# power-converter.net
KiCad netlist of a schematic drawn in EAGLE
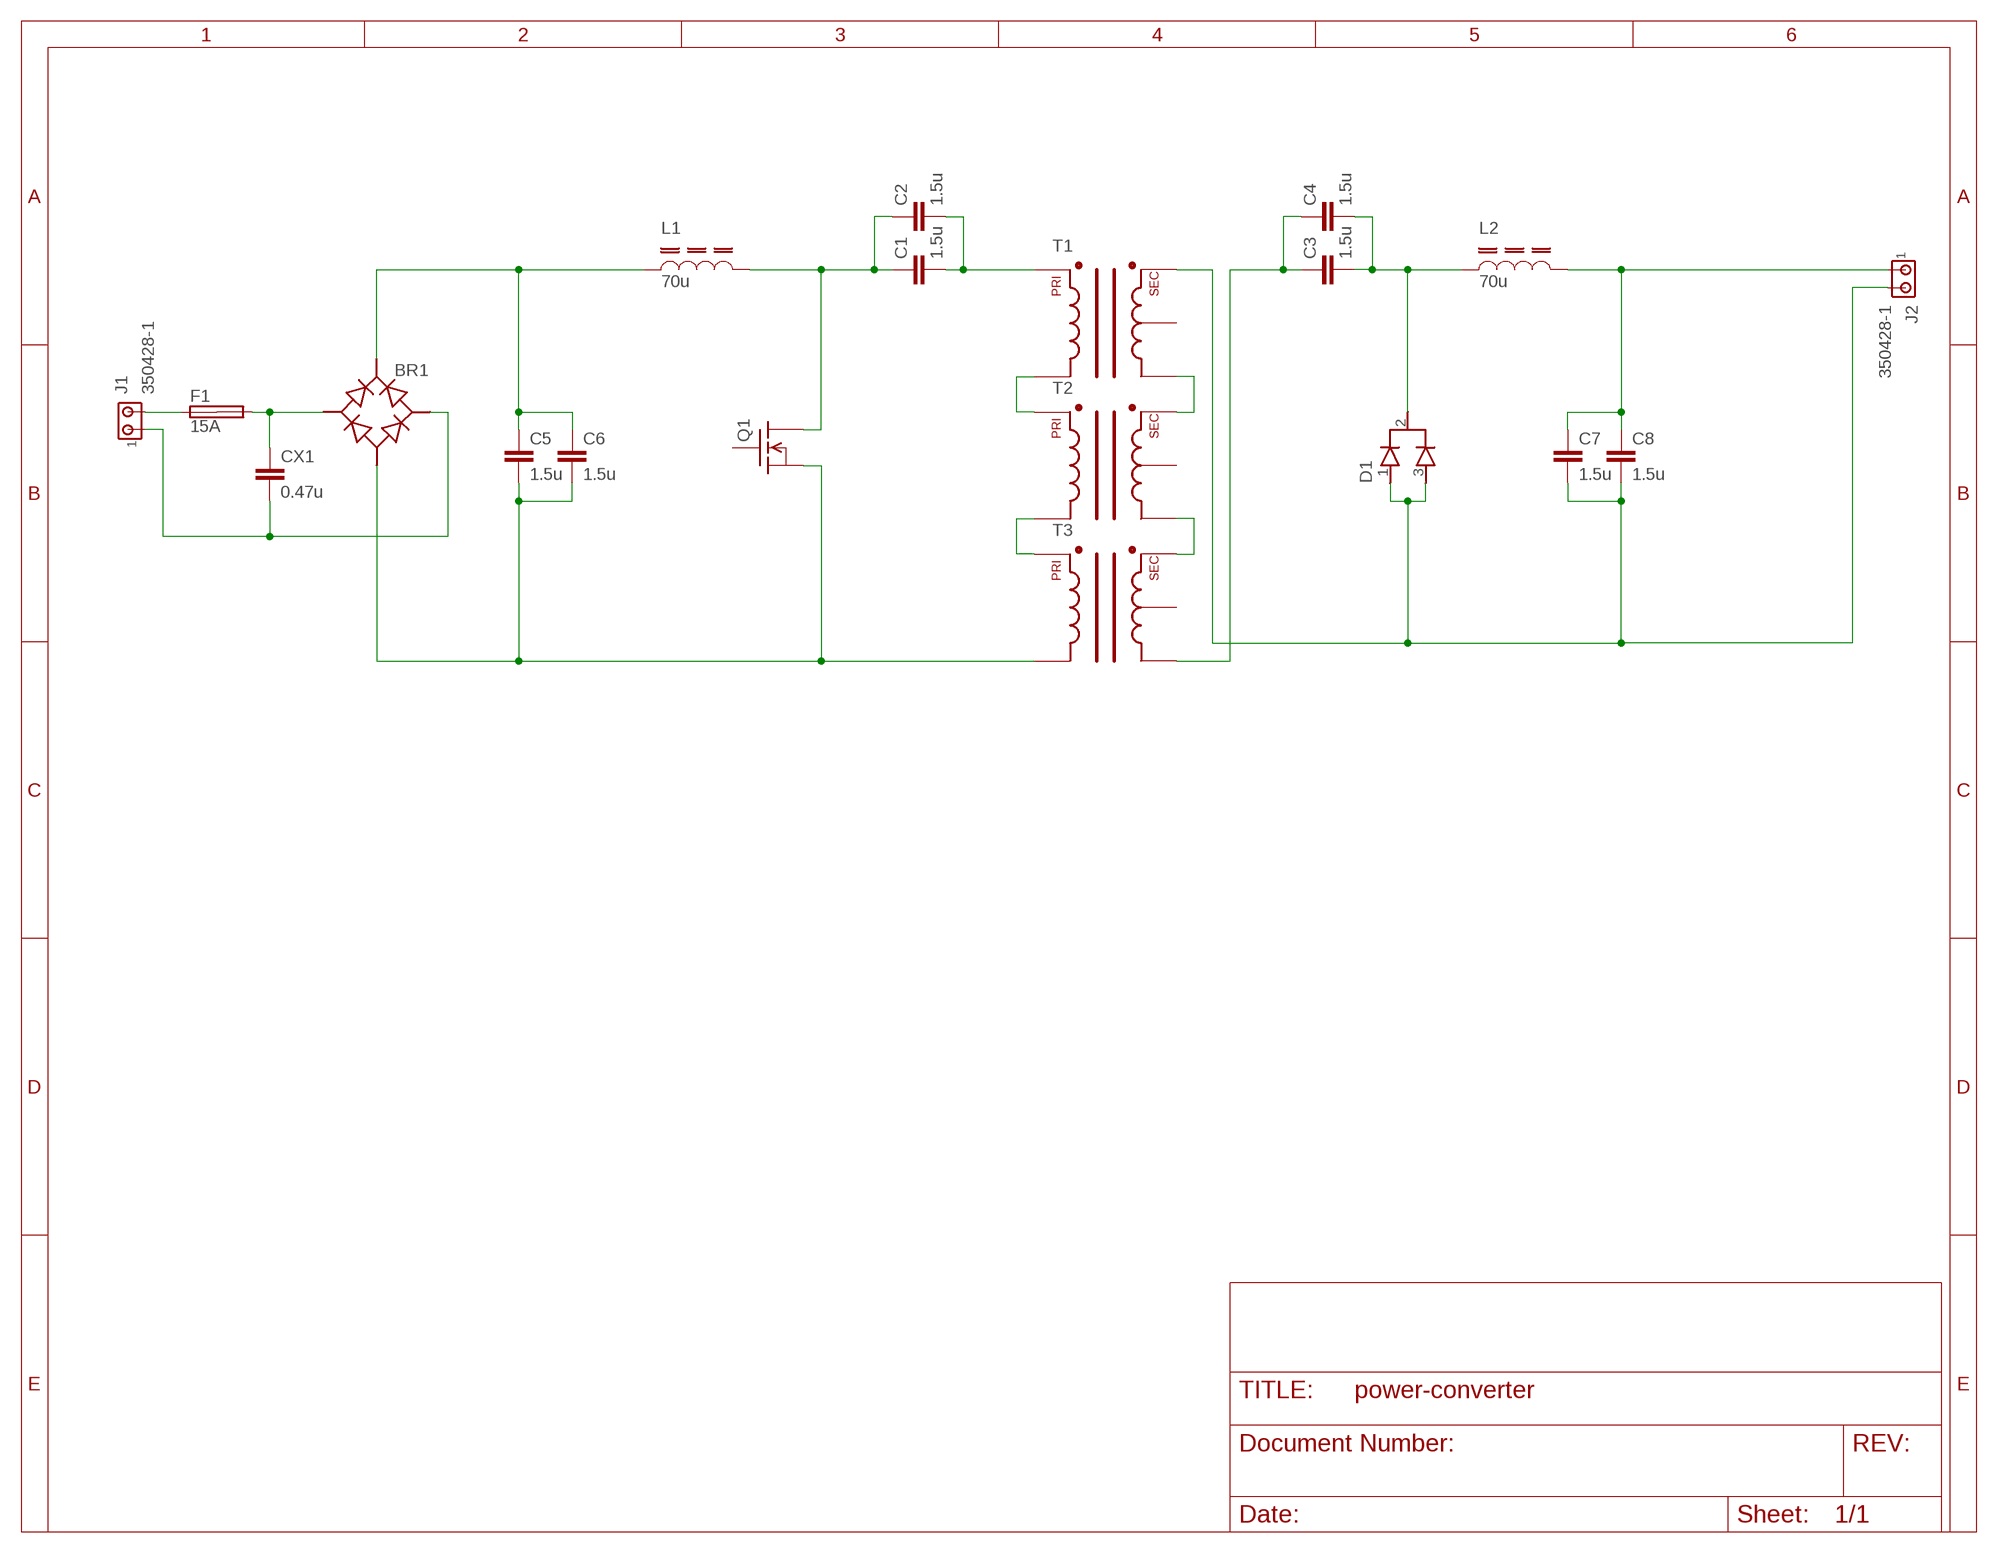
[diagram p0: schematic, sheet 1]

(export (version "E")
  (design (tool "Eeschema 10.0.6"))
  (components
    (comp (ref "BR1")
      (value "DIODE_BRIDGE_RECTIFIERLVB2560")
      (footprint "eagle-import:GSIB-5S")
      (fields (field (name "PARTNUM") "LVB2560"))
      (libsource (lib "eagle-import") (part "DIODE_BRIDGE_RECTIFIERLVB2560"))
    )
    (comp (ref "C1")
      (value "1.5u")
      (footprint "eagle-import:PANASONIC-ECWF-2155-B")
      (fields (field (name "PARTNUM") "ECWF2155XB"))
      (libsource (lib "eagle-import") (part "PANASONIC-ECWF-2155-B"))
    )
    (comp (ref "C2")
      (value "1.5u")
      (footprint "eagle-import:PANASONIC-ECWF-2155-B")
      (fields (field (name "PARTNUM") "ECWF2155XB"))
      (libsource (lib "eagle-import") (part "PANASONIC-ECWF-2155-B"))
    )
    (comp (ref "C3")
      (value "1.5u")
      (footprint "eagle-import:PANASONIC-ECWF-2155-B")
      (fields (field (name "PARTNUM") "ECWF2155XB"))
      (libsource (lib "eagle-import") (part "PANASONIC-ECWF-2155-B"))
    )
    (comp (ref "C4")
      (value "1.5u")
      (footprint "eagle-import:PANASONIC-ECWF-2155-B")
      (fields (field (name "PARTNUM") "ECWF2155XB"))
      (libsource (lib "eagle-import") (part "PANASONIC-ECWF-2155-B"))
    )
    (comp (ref "C5")
      (value "1.5u")
      (footprint "eagle-import:PANASONIC-ECWF-2155-B")
      (fields (field (name "PARTNUM") "ECWF2155XB"))
      (libsource (lib "eagle-import") (part "PANASONIC-ECWF-2155-B"))
    )
    (comp (ref "C6")
      (value "1.5u")
      (footprint "eagle-import:PANASONIC-ECWF-2155-B")
      (fields (field (name "PARTNUM") "ECWF2155XB"))
      (libsource (lib "eagle-import") (part "PANASONIC-ECWF-2155-B"))
    )
    (comp (ref "C7")
      (value "1.5u")
      (footprint "eagle-import:PANASONIC-ECWF-2155-B")
      (fields (field (name "PARTNUM") "ECWF2155XB"))
      (libsource (lib "eagle-import") (part "PANASONIC-ECWF-2155-B"))
    )
    (comp (ref "C8")
      (value "1.5u")
      (footprint "eagle-import:PANASONIC-ECWF-2155-B")
      (fields (field (name "PARTNUM") "ECWF2155XB"))
      (libsource (lib "eagle-import") (part "PANASONIC-ECWF-2155-B"))
    )
    (comp (ref "CX1")
      (value "0.47u")
      (footprint "eagle-import:XC22B7")
      (fields (field (name "PARTNUM") "PHE840MY6470MD14R06L2"))
      (libsource (lib "eagle-import") (part "CXXC22B7"))
    )
    (comp (ref "D1")
      (value "DIODE-COMMON_CATHODETO-247")
      (footprint "eagle-import:TO247BV")
      (fields (field (name "MANUF") "CREE") (field (name "PARTNUM") "C3D20060D"))
      (libsource (lib "eagle-import") (part "DIODE-COMMON_CATHODETO-247"))
    )
    (comp (ref "F1")
      (value "15A")
      (footprint "eagle-import:SH32")
      (fields (field (name "MPN") "10207101009"))
      (libsource (lib "eagle-import") (part "SH32"))
    )
    (comp (ref "J1")
      (value "350428-1")
      (footprint "eagle-import:350428-1")
      (fields (field (name "MF") "TYCO ELECTRONICS"))
      (libsource (lib "eagle-import") (part "350428-1"))
    )
    (comp (ref "J2")
      (value "350428-1")
      (footprint "eagle-import:350428-1")
      (fields (field (name "MF") "TYCO ELECTRONICS"))
      (libsource (lib "eagle-import") (part "350428-1"))
    )
    (comp (ref "L1")
      (value "70u")
      (footprint "eagle-import:COIL-WINDING-SPECIALIST_E70340-016")
      (fields (field (name "PARTNUM") "E70340-016"))
      (libsource (lib "eagle-import") (part "COIL-WINDING-SPECIALIST_E70340-016"))
    )
    (comp (ref "L2")
      (value "70u")
      (footprint "eagle-import:COIL-WINDING-SPECIALIST_E70340-016")
      (fields (field (name "PARTNUM") "E70340-016"))
      (libsource (lib "eagle-import") (part "COIL-WINDING-SPECIALIST_E70340-016"))
    )
    (comp (ref "Q1")
      (value "N-MOS(G,D,S)TO-220A")
      (footprint "eagle-import:TO220AV")
      (fields (field (name "PARTNUM") "STP57N65M5"))
      (libsource (lib "eagle-import") (part "N-MOS(G,D,S)TO-220A"))
    )
    (comp (ref "T1")
      (value "PAYTON_755001")
      (footprint "eagle-import:PAYTON_755001")
      (fields (field (name "PARTNUM") "755001"))
      (libsource (lib "eagle-import") (part "PAYTON_755001"))
    )
    (comp (ref "T2")
      (value "PAYTON_755001")
      (footprint "eagle-import:PAYTON_755001")
      (fields (field (name "PARTNUM") "755001"))
      (libsource (lib "eagle-import") (part "PAYTON_755001"))
    )
    (comp (ref "T3")
      (value "PAYTON_755001")
      (footprint "eagle-import:PAYTON_755001")
      (fields (field (name "PARTNUM") "755001"))
      (libsource (lib "eagle-import") (part "PAYTON_755001"))
    )
  )
  (nets
    (net (code "1") (name "Net-(BR1-PadAC1)") (class "Default")
      (node (ref "BR1") (pin "AC1") (pinfunction "AC1_AC1") (pintype "passive"))
      (node (ref "CX1") (pin "1") (pinfunction "1_1") (pintype "passive"))
      (node (ref "F1") (pin "2A") (pinfunction "2A_2A") (pintype "passive"))
    )
    (net (code "2") (name "Net-(BR1-PadAC2)") (class "Default")
      (node (ref "BR1") (pin "AC2") (pinfunction "AC2_AC2") (pintype "passive"))
      (node (ref "CX1") (pin "2") (pinfunction "2_2") (pintype "passive"))
      (node (ref "J1") (pin "1") (pinfunction "1_1") (pintype "passive"))
    )
    (net (code "3") (name "Net-(BR1-PadPOS)") (class "Default")
      (node (ref "BR1") (pin "POS") (pinfunction "POS_POS") (pintype "passive"))
      (node (ref "C5") (pin "1") (pinfunction "1_1") (pintype "passive"))
      (node (ref "C6") (pin "1") (pinfunction "1_1") (pintype "passive"))
      (node (ref "L1") (pin "1_B") (pinfunction "P$1_1_B") (pintype "passive"))
      (node (ref "L1") (pin "1_T") (pinfunction "P$1_1_T") (pintype "passive"))
    )
    (net (code "4") (name "Net-(C7-Pad1)") (class "Default")
      (node (ref "C7") (pin "1") (pinfunction "1_1") (pintype "passive"))
      (node (ref "C8") (pin "1") (pinfunction "1_1") (pintype "passive"))
      (node (ref "J2") (pin "1") (pinfunction "1_1") (pintype "passive"))
      (node (ref "L2") (pin "2_B") (pinfunction "P$2_2_B") (pintype "passive"))
      (node (ref "L2") (pin "2_T") (pinfunction "P$2_2_T") (pintype "passive"))
    )
    (net (code "5") (name "Net-(D1-CATHODE)") (class "Default")
      (node (ref "C3") (pin "2") (pinfunction "2_2") (pintype "passive"))
      (node (ref "C4") (pin "2") (pinfunction "2_2") (pintype "passive"))
      (node (ref "D1") (pin "2") (pinfunction "CATHODE_2") (pintype "passive"))
      (node (ref "L2") (pin "1_B") (pinfunction "P$1_1_B") (pintype "passive"))
      (node (ref "L2") (pin "1_T") (pinfunction "P$1_1_T") (pintype "passive"))
    )
    (net (code "6") (name "Net-(F1-Pad1A)") (class "Default")
      (node (ref "F1") (pin "1A") (pinfunction "1A_1A") (pintype "passive"))
      (node (ref "J1") (pin "2") (pinfunction "2_2") (pintype "passive"))
    )
    (net (code "7") (name "Net-(Q1-D)") (class "Default")
      (node (ref "C1") (pin "1") (pinfunction "1_1") (pintype "passive"))
      (node (ref "C2") (pin "1") (pinfunction "1_1") (pintype "passive"))
      (node (ref "L1") (pin "2_B") (pinfunction "P$2_2_B") (pintype "passive"))
      (node (ref "L1") (pin "2_T") (pinfunction "P$2_2_T") (pintype "passive"))
      (node (ref "Q1") (pin "2") (pinfunction "D_2") (pintype "passive"))
    )
    (net (code "8") (name "Net-(Q1-S)") (class "Default")
      (node (ref "BR1") (pin "NEG") (pinfunction "NEG_NEG") (pintype "passive"))
      (node (ref "C5") (pin "2") (pinfunction "2_2") (pintype "passive"))
      (node (ref "C6") (pin "2") (pinfunction "2_2") (pintype "passive"))
      (node (ref "Q1") (pin "3") (pinfunction "S_3") (pintype "passive"))
      (node (ref "T3") (pin "8,9") (pinfunction "PRI_UNDOT_8,9") (pintype "passive"))
    )
    (net (code "9") (name "Net-(T1-PRI_DOT)") (class "Default")
      (node (ref "C1") (pin "2") (pinfunction "2_2") (pintype "passive"))
      (node (ref "C2") (pin "2") (pinfunction "2_2") (pintype "passive"))
      (node (ref "T1") (pin "1,2") (pinfunction "PRI_DOT_1,2") (pintype "passive"))
    )
    (net (code "10") (name "Net-(T1-PRI_UNDOT)") (class "Default")
      (node (ref "T1") (pin "8,9") (pinfunction "PRI_UNDOT_8,9") (pintype "passive"))
      (node (ref "T2") (pin "1,2") (pinfunction "PRI_DOT_1,2") (pintype "passive"))
    )
    (net (code "11") (name "Net-(T1-SEC_DOT)") (class "Default")
      (node (ref "C7") (pin "2") (pinfunction "2_2") (pintype "passive"))
      (node (ref "C8") (pin "2") (pinfunction "2_2") (pintype "passive"))
      (node (ref "D1") (pin "1") (pinfunction "ANODE_1") (pintype "passive"))
      (node (ref "D1") (pin "3") (pinfunction "ANODE_3") (pintype "passive"))
      (node (ref "J2") (pin "2") (pinfunction "2_2") (pintype "passive"))
      (node (ref "T1") (pin "10,11,12") (pinfunction "SEC_DOT_10,11,12") (pintype "passive"))
    )
    (net (code "12") (name "Net-(T1-SEC_UNDOT)") (class "Default")
      (node (ref "T1") (pin "16,17,18") (pinfunction "SEC_UNDOT_16,17,18") (pintype "passive"))
      (node (ref "T2") (pin "10,11,12") (pinfunction "SEC_DOT_10,11,12") (pintype "passive"))
    )
    (net (code "13") (name "Net-(T2-PRI_UNDOT)") (class "Default")
      (node (ref "T2") (pin "8,9") (pinfunction "PRI_UNDOT_8,9") (pintype "passive"))
      (node (ref "T3") (pin "1,2") (pinfunction "PRI_DOT_1,2") (pintype "passive"))
    )
    (net (code "14") (name "Net-(T2-SEC_UNDOT)") (class "Default")
      (node (ref "T2") (pin "16,17,18") (pinfunction "SEC_UNDOT_16,17,18") (pintype "passive"))
      (node (ref "T3") (pin "10,11,12") (pinfunction "SEC_DOT_10,11,12") (pintype "passive"))
    )
    (net (code "15") (name "Net-(T3-SEC_UNDOT)") (class "Default")
      (node (ref "C3") (pin "1") (pinfunction "1_1") (pintype "passive"))
      (node (ref "C4") (pin "1") (pinfunction "1_1") (pintype "passive"))
      (node (ref "T3") (pin "16,17,18") (pinfunction "SEC_UNDOT_16,17,18") (pintype "passive"))
    )
    (net (code "16") (name "unconnected-(F1-Pad1B)") (class "Default")
      (node (ref "F1") (pin "1B") (pinfunction "1B_1B") (pintype "passive"))
    )
    (net (code "17") (name "unconnected-(F1-Pad2B)") (class "Default")
      (node (ref "F1") (pin "2B") (pinfunction "2B_2B") (pintype "passive"))
    )
    (net (code "18") (name "unconnected-(Q1-G-Pad1)") (class "Default")
      (node (ref "Q1") (pin "1") (pinfunction "G_1") (pintype "passive"))
    )
    (net (code "19") (name "unconnected-(T1-SEC_CENTERTAP-Pad13,14,15)") (class "Default")
      (node (ref "T1") (pin "13,14,15") (pinfunction "SEC_CENTERTAP_13,14,15") (pintype "passive"))
    )
    (net (code "20") (name "unconnected-(T2-SEC_CENTERTAP-Pad13,14,15)") (class "Default")
      (node (ref "T2") (pin "13,14,15") (pinfunction "SEC_CENTERTAP_13,14,15") (pintype "passive"))
    )
    (net (code "21") (name "unconnected-(T3-SEC_CENTERTAP-Pad13,14,15)") (class "Default")
      (node (ref "T3") (pin "13,14,15") (pinfunction "SEC_CENTERTAP_13,14,15") (pintype "passive"))
    )
  )
)
